# basic_pcb.net
KiCad netlist of a schematic drawn in EAGLE
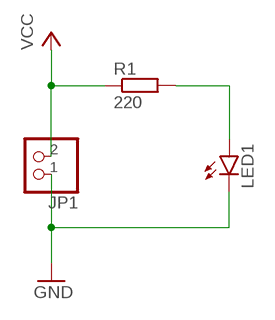
[diagram p0: schematic, sheet 1]

(export (version "E")
  (design (tool "Eeschema 10.0.6"))
  (components
    (comp (ref "JP1")
      (value "PINHD-1X2")
      (footprint "eagle-import:1X02")
      (libsource (lib "eagle-import") (part "PINHD-1X2"))
    )
    (comp (ref "LED1")
      (value "LED3MM")
      (footprint "eagle-import:LED3MM")
      (libsource (lib "eagle-import") (part "LED3MM"))
    )
    (comp (ref "R1")
      (value "220")
      (footprint "eagle-import:0204_7")
      (libsource (lib "eagle-import") (part "R-EU_0204/7"))
    )
  )
  (nets
    (net (code "1") (name "GND") (class "Default")
      (node (ref "JP1") (pin "1") (pinfunction "1_1") (pintype "passive"))
      (node (ref "LED1") (pin "K") (pinfunction "C_K") (pintype "passive"))
    )
    (net (code "2") (name "Net-(LED1-PadA)") (class "Default")
      (node (ref "LED1") (pin "A") (pinfunction "A_A") (pintype "passive"))
      (node (ref "R1") (pin "2") (pinfunction "2_2") (pintype "passive"))
    )
    (net (code "3") (name "VCC") (class "Default")
      (node (ref "JP1") (pin "2") (pinfunction "2_2") (pintype "passive"))
      (node (ref "R1") (pin "1") (pinfunction "1_1") (pintype "passive"))
    )
  )
)
